# Input.net
KiCad netlist of a schematic drawn in Altium Designer
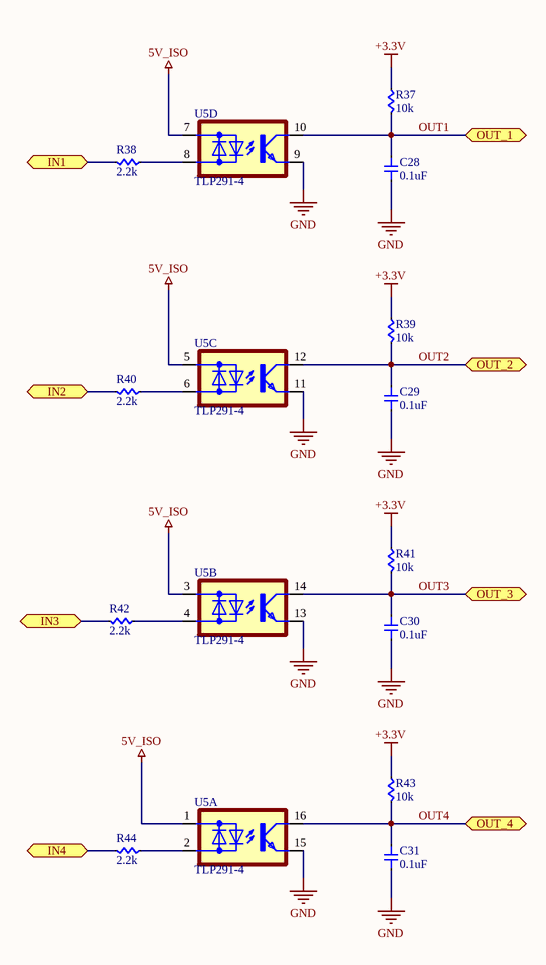
[diagram p0: Input.SchDoc]

(export (version "E")
  (design (tool "Eeschema 10.0.6"))
  (components
    (comp (ref "C28")
      (value "0.1uF")
      (footprint "Cap 0603")
      (description "Capacitor SMD 0603")
      (libsource (lib "Altium_Lib_PTK") (part "Cap 0603"))
    )
    (comp (ref "C29")
      (value "0.1uF")
      (footprint "Cap 0603")
      (description "Capacitor SMD 0603")
      (libsource (lib "Altium_Lib_PTK") (part "Cap 0603"))
    )
    (comp (ref "C30")
      (value "0.1uF")
      (footprint "Cap 0603")
      (description "Capacitor SMD 0603")
      (libsource (lib "Altium_Lib_PTK") (part "Cap 0603"))
    )
    (comp (ref "C31")
      (value "0.1uF")
      (footprint "Cap 0603")
      (description "Capacitor SMD 0603")
      (libsource (lib "Altium_Lib_PTK") (part "Cap 0603"))
    )
    (comp (ref "R37")
      (value "10k")
      (footprint "RES 0603")
      (description "RES SMD 0603")
      (fields
        (field (name "MANUFACTURER") "Vishay Dale")
        (field (name "MANUFACTURER PART NUMBER") "CRCW040210K0FKED")
      )
      (libsource (lib "Altium_Lib_PTK") (part "RES 0603"))
    )
    (comp (ref "R38")
      (value "2.2k")
      (footprint "RES 0603")
      (description "RES SMD 0603")
      (fields
        (field (name "MANUFACTURER") "Vishay Dale")
        (field (name "MANUFACTURER PART NUMBER") "CRCW040210K0FKED")
      )
      (libsource (lib "Altium_Lib_PTK") (part "RES 0603"))
    )
    (comp (ref "R39")
      (value "10k")
      (footprint "RES 0603")
      (description "RES SMD 0603")
      (fields
        (field (name "MANUFACTURER") "Vishay Dale")
        (field (name "MANUFACTURER PART NUMBER") "CRCW040210K0FKED")
      )
      (libsource (lib "Altium_Lib_PTK") (part "RES 0603"))
    )
    (comp (ref "R40")
      (value "2.2k")
      (footprint "RES 0603")
      (description "RES SMD 0603")
      (fields
        (field (name "MANUFACTURER") "Vishay Dale")
        (field (name "MANUFACTURER PART NUMBER") "CRCW040210K0FKED")
      )
      (libsource (lib "Altium_Lib_PTK") (part "RES 0603"))
    )
    (comp (ref "R41")
      (value "10k")
      (footprint "RES 0603")
      (description "RES SMD 0603")
      (fields
        (field (name "MANUFACTURER") "Vishay Dale")
        (field (name "MANUFACTURER PART NUMBER") "CRCW040210K0FKED")
      )
      (libsource (lib "Altium_Lib_PTK") (part "RES 0603"))
    )
    (comp (ref "R42")
      (value "2.2k")
      (footprint "RES 0603")
      (description "RES SMD 0603")
      (fields
        (field (name "MANUFACTURER") "Vishay Dale")
        (field (name "MANUFACTURER PART NUMBER") "CRCW040210K0FKED")
      )
      (libsource (lib "Altium_Lib_PTK") (part "RES 0603"))
    )
    (comp (ref "R43")
      (value "10k")
      (footprint "RES 0603")
      (description "RES SMD 0603")
      (fields
        (field (name "MANUFACTURER") "Vishay Dale")
        (field (name "MANUFACTURER PART NUMBER") "CRCW040210K0FKED")
      )
      (libsource (lib "Altium_Lib_PTK") (part "RES 0603"))
    )
    (comp (ref "R44")
      (value "2.2k")
      (footprint "RES 0603")
      (description "RES SMD 0603")
      (fields
        (field (name "MANUFACTURER") "Vishay Dale")
        (field (name "MANUFACTURER PART NUMBER") "CRCW040210K0FKED")
      )
      (libsource (lib "Altium_Lib_PTK") (part "RES 0603"))
    )
    (comp (ref "U5")
      (value "TLP291-4")
      (footprint "SOP16_TLP2xx")
      (description "Optoisolator Transistor Output 2500Vrms 4 Channel 16-SOP")
      (fields (field (name "MF") "Toshiba Semiconductor") (field (name "MP") "TLP 280-4"))
      (libsource (lib "Altium_Lib_PTK") (part "OPTO TLP291-4"))
    )
  )
  (nets
    (net (code "1") (name "+3.3V") (class "Default")
      (node (ref "R37") (pin "1") (pinfunction "1_1") (pintype "passive"))
      (node (ref "R39") (pin "1") (pinfunction "1_1") (pintype "passive"))
      (node (ref "R41") (pin "1") (pinfunction "1_1") (pintype "passive"))
      (node (ref "R43") (pin "1") (pinfunction "1_1") (pintype "passive"))
    )
    (net (code "2") (name "/IN1") (class "Default")
      (node (ref "R38") (pin "2") (pinfunction "2_2") (pintype "passive"))
    )
    (net (code "3") (name "/IN2") (class "Default")
      (node (ref "R40") (pin "2") (pinfunction "2_2") (pintype "passive"))
    )
    (net (code "4") (name "/IN3") (class "Default")
      (node (ref "R42") (pin "2") (pinfunction "2_2") (pintype "passive"))
    )
    (net (code "5") (name "/IN4") (class "Default")
      (node (ref "R44") (pin "2") (pinfunction "2_2") (pintype "passive"))
    )
    (net (code "6") (name "/OUT1") (class "Default")
      (node (ref "C28") (pin "1") (pinfunction "1_1") (pintype "passive"))
      (node (ref "R37") (pin "2") (pinfunction "2_2") (pintype "passive"))
      (node (ref "U5") (pin "10") (pinfunction "C_10") (pintype "passive"))
    )
    (net (code "7") (name "/OUT2") (class "Default")
      (node (ref "C29") (pin "1") (pinfunction "1_1") (pintype "passive"))
      (node (ref "R39") (pin "2") (pinfunction "2_2") (pintype "passive"))
      (node (ref "U5") (pin "12") (pinfunction "C_12") (pintype "passive"))
    )
    (net (code "8") (name "/OUT3") (class "Default")
      (node (ref "C30") (pin "1") (pinfunction "1_1") (pintype "passive"))
      (node (ref "R41") (pin "2") (pinfunction "2_2") (pintype "passive"))
      (node (ref "U5") (pin "14") (pinfunction "C_14") (pintype "passive"))
    )
    (net (code "9") (name "/OUT4") (class "Default")
      (node (ref "C31") (pin "1") (pinfunction "1_1") (pintype "passive"))
      (node (ref "R43") (pin "2") (pinfunction "2_2") (pintype "passive"))
      (node (ref "U5") (pin "16") (pinfunction "C_16") (pintype "passive"))
    )
    (net (code "10") (name "5V_ISO") (class "Default")
      (node (ref "U5") (pin "1") (pinfunction "AC1_1") (pintype "passive"))
      (node (ref "U5") (pin "3") (pinfunction "AC1_3") (pintype "passive"))
      (node (ref "U5") (pin "5") (pinfunction "AC1_5") (pintype "passive"))
      (node (ref "U5") (pin "7") (pinfunction "AC1_7") (pintype "passive"))
    )
    (net (code "11") (name "GND") (class "Default")
      (node (ref "C28") (pin "2") (pinfunction "2_2") (pintype "passive"))
      (node (ref "C29") (pin "2") (pinfunction "2_2") (pintype "passive"))
      (node (ref "C30") (pin "2") (pinfunction "2_2") (pintype "passive"))
      (node (ref "C31") (pin "2") (pinfunction "2_2") (pintype "passive"))
      (node (ref "U5") (pin "11") (pinfunction "E_11") (pintype "passive"))
      (node (ref "U5") (pin "13") (pinfunction "E_13") (pintype "passive"))
      (node (ref "U5") (pin "15") (pinfunction "E_15") (pintype "passive"))
      (node (ref "U5") (pin "9") (pinfunction "E_9") (pintype "passive"))
    )
    (net (code "12") (name "Net-(U5A-AC2)") (class "Default")
      (node (ref "R44") (pin "1") (pinfunction "1_1") (pintype "passive"))
      (node (ref "U5") (pin "2") (pinfunction "AC2_2") (pintype "passive"))
    )
    (net (code "13") (name "Net-(U5B-AC2)") (class "Default")
      (node (ref "R42") (pin "1") (pinfunction "1_1") (pintype "passive"))
      (node (ref "U5") (pin "4") (pinfunction "AC2_4") (pintype "passive"))
    )
    (net (code "14") (name "Net-(U5C-AC2)") (class "Default")
      (node (ref "R40") (pin "1") (pinfunction "1_1") (pintype "passive"))
      (node (ref "U5") (pin "6") (pinfunction "AC2_6") (pintype "passive"))
    )
    (net (code "15") (name "Net-(U5D-AC2)") (class "Default")
      (node (ref "R38") (pin "1") (pinfunction "1_1") (pintype "passive"))
      (node (ref "U5") (pin "8") (pinfunction "AC2_8") (pintype "passive"))
    )
  )
)
